# clock.net
KiCad netlist of a schematic drawn in Altium Designer
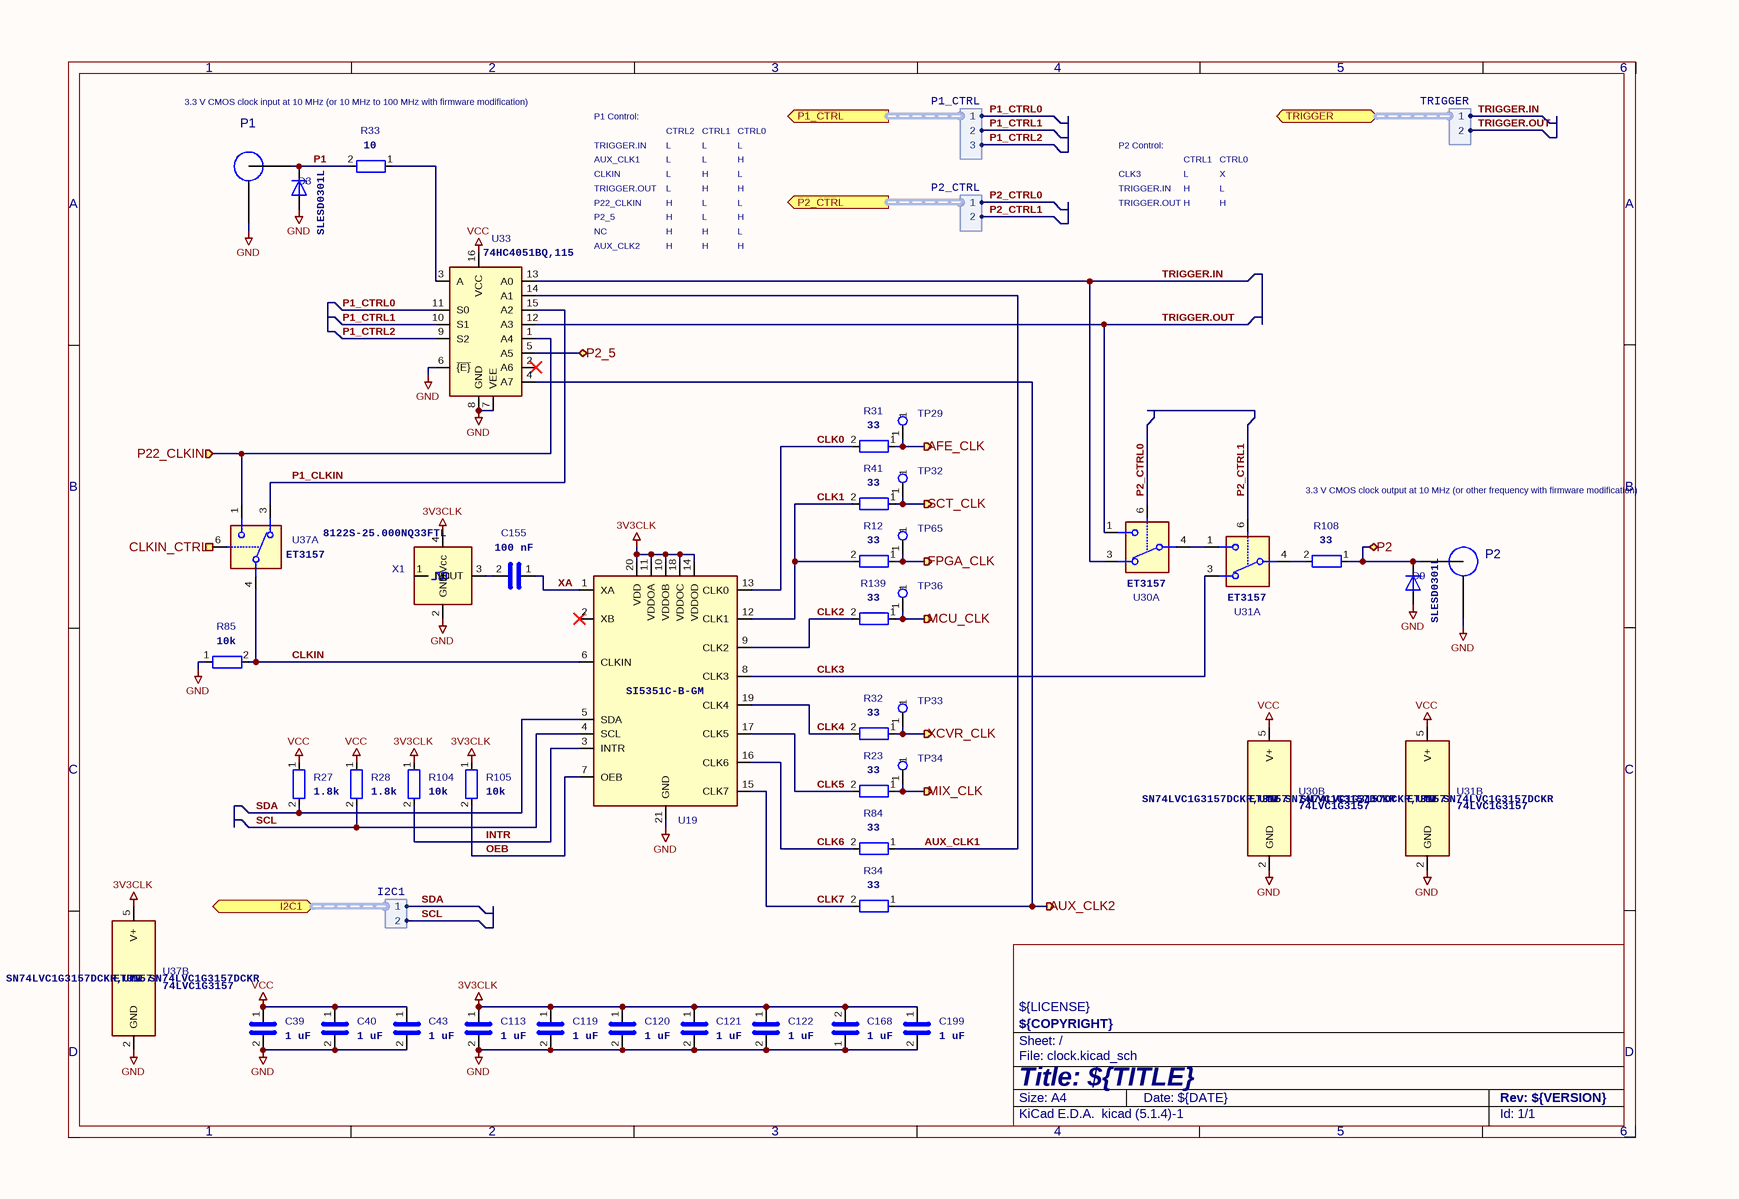
[diagram p0: clock.SchDoc]

(export (version "E")
  (design (tool "Eeschema 10.0.6"))
  (components
    (comp (ref "C39")
      (value "1 uF")
      (footprint "C_0402_1005Metric")
      (fields (field (name "MANUFACTURER") "Samsung") (field (name "PART NUMBER") "CL05A105KA5NQNC"))
      (libsource (lib "Device") (part "C"))
    )
    (comp (ref "C40")
      (value "1 uF")
      (footprint "C_0402_1005Metric")
      (fields (field (name "MANUFACTURER") "Samsung") (field (name "PART NUMBER") "CL05A105KA5NQNC"))
      (libsource (lib "Device") (part "C"))
    )
    (comp (ref "C43")
      (value "1 uF")
      (footprint "C_0402_1005Metric")
      (fields (field (name "MANUFACTURER") "Samsung") (field (name "PART NUMBER") "CL05A105KA5NQNC"))
      (libsource (lib "Device") (part "C"))
    )
    (comp (ref "C113")
      (value "1 uF")
      (footprint "C_0402_1005Metric")
      (fields (field (name "MANUFACTURER") "Samsung") (field (name "PART NUMBER") "CL05A105KA5NQNC"))
      (libsource (lib "Device") (part "C"))
    )
    (comp (ref "C119")
      (value "1 uF")
      (footprint "C_0402_1005Metric")
      (fields (field (name "MANUFACTURER") "Samsung") (field (name "PART NUMBER") "CL05A105KA5NQNC"))
      (libsource (lib "Device") (part "C"))
    )
    (comp (ref "C120")
      (value "1 uF")
      (footprint "C_0402_1005Metric")
      (fields (field (name "MANUFACTURER") "Samsung") (field (name "PART NUMBER") "CL05A105KA5NQNC"))
      (libsource (lib "Device") (part "C"))
    )
    (comp (ref "C121")
      (value "1 uF")
      (footprint "C_0402_1005Metric")
      (fields (field (name "MANUFACTURER") "Samsung") (field (name "PART NUMBER") "CL05A105KA5NQNC"))
      (libsource (lib "Device") (part "C"))
    )
    (comp (ref "C122")
      (value "1 uF")
      (footprint "C_0402_1005Metric")
      (fields (field (name "MANUFACTURER") "Samsung") (field (name "PART NUMBER") "CL05A105KA5NQNC"))
      (libsource (lib "Device") (part "C"))
    )
    (comp (ref "C155")
      (value "100 nF")
      (footprint "C_0402_1005Metric")
      (fields (field (name "MANUFACTURER") "Samsung") (field (name "PART NUMBER") "CL05A104KA5NNNC"))
      (libsource (lib "Device") (part "C"))
    )
    (comp (ref "C168")
      (value "1 uF")
      (footprint "C_0402_1005Metric")
      (fields (field (name "MANUFACTURER") "Samsung") (field (name "PART NUMBER") "CL05A105KA5NQNC"))
      (libsource (lib "Device") (part "C"))
    )
    (comp (ref "C199")
      (value "1 uF")
      (footprint "C_0402_1005Metric")
      (fields (field (name "MANUFACTURER") "Samsung") (field (name "PART NUMBER") "CL05A105KA5NQNC"))
      (libsource (lib "Device") (part "C"))
    )
    (comp (ref "D3")
      (value "TVS")
      (footprint "TSLP-2-19")
      (fields (field (name "MANUFACTURER") "Slkor") (field (name "PART NUMBER") "SLESD0301L"))
      (libsource (lib "Device") (part "D_Zener"))
    )
    (comp (ref "D9")
      (value "TVS")
      (footprint "TSLP-2-19")
      (fields (field (name "MANUFACTURER") "Slkor") (field (name "PART NUMBER") "SLESD0301L"))
      (libsource (lib "Device") (part "D_Zener"))
    )
    (comp (ref "P1")
      (value "SMA")
      (footprint "SMA_MyAntenna_A-SMA-KE-16.5A_EdgeMount")
      (fields (field (name "MANUFACTURER") "MyAntenna") (field (name "PART NUMBER") "A-SMA-KE-16.5A"))
      (libsource (lib "hackrf") (part "GSG-RF-CONN"))
    )
    (comp (ref "P2")
      (value "SMA")
      (footprint "SMA_MyAntenna_A-SMA-KE-16.5A_EdgeMount")
      (fields (field (name "MANUFACTURER") "MyAntenna") (field (name "PART NUMBER") "A-SMA-KE-16.5A"))
      (libsource (lib "hackrf") (part "GSG-RF-CONN"))
    )
    (comp (ref "R12")
      (value "33")
      (footprint "R_0201_0603Metric")
      (fields (field (name "MANUFACTURER") "Yageo") (field (name "PART NUMBER") "RC0201JR-0733RL"))
      (libsource (lib "") (part "R_1"))
    )
    (comp (ref "R23")
      (value "33")
      (footprint "R_0201_0603Metric")
      (fields (field (name "MANUFACTURER") "Yageo") (field (name "PART NUMBER") "RC0201JR-0733RL"))
      (libsource (lib "") (part "R_1"))
    )
    (comp (ref "R27")
      (value "1.8k")
      (footprint "R_0402_1005Metric")
      (fields (field (name "MANUFACTURER") "Yageo") (field (name "PART NUMBER") "RC0402JR-071K8L"))
      (libsource (lib "Device") (part "R"))
    )
    (comp (ref "R28")
      (value "1.8k")
      (footprint "R_0402_1005Metric")
      (fields (field (name "MANUFACTURER") "Yageo") (field (name "PART NUMBER") "RC0402JR-071K8L"))
      (libsource (lib "Device") (part "R"))
    )
    (comp (ref "R31")
      (value "33")
      (footprint "R_0201_0603Metric")
      (fields (field (name "MANUFACTURER") "Yageo") (field (name "PART NUMBER") "RC0201JR-0733RL"))
      (libsource (lib "") (part "R_1"))
    )
    (comp (ref "R32")
      (value "33")
      (footprint "R_0201_0603Metric")
      (fields (field (name "MANUFACTURER") "Yageo") (field (name "PART NUMBER") "RC0201JR-0733RL"))
      (libsource (lib "") (part "R_1"))
    )
    (comp (ref "R33")
      (value "10")
      (footprint "R_0201_0603Metric")
      (fields (field (name "MANUFACTURER") "Yageo") (field (name "PART NUMBER") "RC0201JR-0710RL"))
      (libsource (lib "") (part "R_1"))
    )
    (comp (ref "R34")
      (value "33")
      (footprint "R_0201_0603Metric")
      (fields (field (name "MANUFACTURER") "Yageo") (field (name "PART NUMBER") "RC0201JR-0733RL"))
      (libsource (lib "") (part "R_1"))
    )
    (comp (ref "R41")
      (value "33")
      (footprint "R_0201_0603Metric")
      (fields (field (name "MANUFACTURER") "Yageo") (field (name "PART NUMBER") "RC0201JR-0733RL"))
      (libsource (lib "") (part "R_1"))
    )
    (comp (ref "R84")
      (value "33")
      (footprint "R_0201_0603Metric")
      (fields (field (name "MANUFACTURER") "Yageo") (field (name "PART NUMBER") "RC0201JR-0733RL"))
      (libsource (lib "") (part "R_1"))
    )
    (comp (ref "R85")
      (value "10k")
      (footprint "R_0402_1005Metric")
      (fields (field (name "MANUFACTURER") "Yageo") (field (name "PART NUMBER") "RC0402JR-0710KL"))
      (libsource (lib "") (part "R_2"))
    )
    (comp (ref "R104")
      (value "10k")
      (footprint "R_0402_1005Metric")
      (fields (field (name "MANUFACTURER") "Yageo") (field (name "PART NUMBER") "RC0402JR-0710KL"))
      (libsource (lib "Device") (part "R"))
    )
    (comp (ref "R105")
      (value "10k")
      (footprint "R_0402_1005Metric")
      (fields (field (name "MANUFACTURER") "Yageo") (field (name "PART NUMBER") "RC0402JR-0710KL"))
      (libsource (lib "Device") (part "R"))
    )
    (comp (ref "R108")
      (value "33")
      (footprint "R_0201_0603Metric")
      (fields (field (name "MANUFACTURER") "Yageo") (field (name "PART NUMBER") "RC0201JR-0733RL"))
      (libsource (lib "") (part "R_1"))
    )
    (comp (ref "R139")
      (value "33")
      (footprint "R_0201_0603Metric")
      (fields (field (name "MANUFACTURER") "Yageo") (field (name "PART NUMBER") "RC0201JR-0733RL"))
      (libsource (lib "") (part "R_1"))
    )
    (comp (ref "TP29")
      (value "TestPoint")
      (footprint "TestPoint_Pad_D1.0mm")
      (libsource (lib "Connector") (part "TestPoint"))
    )
    (comp (ref "TP32")
      (value "TestPoint")
      (footprint "TestPoint_Pad_D1.0mm")
      (libsource (lib "Connector") (part "TestPoint"))
    )
    (comp (ref "TP33")
      (value "TestPoint")
      (footprint "TestPoint_Pad_D1.0mm")
      (libsource (lib "Connector") (part "TestPoint"))
    )
    (comp (ref "TP34")
      (value "TestPoint")
      (footprint "TestPoint_Pad_D1.0mm")
      (libsource (lib "Connector") (part "TestPoint"))
    )
    (comp (ref "TP36")
      (value "TestPoint")
      (footprint "TestPoint_Pad_D1.0mm")
      (libsource (lib "Connector") (part "TestPoint"))
    )
    (comp (ref "TP65")
      (value "TestPoint")
      (footprint "TestPoint_Pad_D1.0mm")
      (libsource (lib "Connector") (part "TestPoint"))
    )
    (comp (ref "U19")
      (value "SI5351C")
      (footprint "QFN-20-1EP_4x4mm_P0.5mm_EP2.7x2.7mm_ThermalVias")
      (fields
        (field (name "MANUFACTURER") "Silicon Laboratories Inc")
        (field (name "PART NUMBER") "SI5351C-B-GM")
      )
      (libsource (lib "Oscillator") (part "Si5351C-B-GM"))
    )
    (comp (ref "U30")
      (value "74LVC1G3157")
      (footprint "SOT-363_SC-70-6")
      (fields
        (field (name "MANUFACTURER") "UMW")
        (field (name "PART NUMBER") "ET3157")
        (field (name "SUBSTITUTION") "SN74LVC1G3157DCKR, TI SN74LVC1G3157DCKR")
      )
      (libsource (lib "Analog_Switch") (part "NC7SB3157P6X"))
    )
    (comp (ref "U31")
      (value "74LVC1G3157")
      (footprint "SOT-363_SC-70-6")
      (fields
        (field (name "MANUFACTURER") "UMW")
        (field (name "PART NUMBER") "ET3157")
        (field (name "SUBSTITUTION") "SN74LVC1G3157DCKR, TI SN74LVC1G3157DCKR")
      )
      (libsource (lib "") (part "NC7SB3157P6X_1"))
    )
    (comp (ref "U33")
      (value "74HC4051")
      (footprint "DHVQFN-16-1EP_2.5x3.5mm_P0.5mm_EP1x2mm")
      (fields (field (name "MANUFACTURER") "Nexperia") (field (name "PART NUMBER") "74HC4051BQ,115"))
      (libsource (lib "74xx") (part "74HC4051"))
    )
    (comp (ref "U37")
      (value "74LVC1G3157")
      (footprint "SOT-363_SC-70-6")
      (fields
        (field (name "MANUFACTURER") "UMW")
        (field (name "PART NUMBER") "ET3157")
        (field (name "SUBSTITUTION") "SN74LVC1G3157DCKR, TI SN74LVC1G3157DCKR")
      )
      (libsource (lib "Analog_Switch") (part "NC7SB3157P6X"))
    )
    (comp (ref "X1")
      (value "TCXO")
      (footprint "Oscillator_SMD_SeikoEpson_TG2520SMN-xxx-xxxxxx-4Pin_2.5x2.0mm")
      (fields (field (name "MANUFACTURER") "HCI") (field (name "PART NUMBER") "8122S-25.000NQ33FTL"))
      (libsource (lib "Oscillator") (part "TG2520SMN-xx.xxxxxxMhz-xxxxNM"))
    )
  )
  (nets
    (net (code "5") (name "/AFE_CLK") (class "Default")
      (node (ref "R31") (pin "1") (pinfunction "1_1") (pintype "passive"))
      (node (ref "TP29") (pin "1") (pinfunction "1_1") (pintype "passive"))
    )
    (net (code "6") (name "/AUX_CLK1") (class "Default")
      (node (ref "R84") (pin "1") (pinfunction "1_1") (pintype "passive"))
      (node (ref "U33") (pin "14") (pinfunction "A1_14") (pintype "passive"))
    )
    (net (code "7") (name "/AUX_CLK2") (class "Default")
      (node (ref "R34") (pin "1") (pinfunction "1_1") (pintype "passive"))
      (node (ref "U33") (pin "4") (pinfunction "A7_4") (pintype "passive"))
    )
    (net (code "8") (name "/CLK0") (class "Default")
      (node (ref "R31") (pin "2") (pinfunction "2_2") (pintype "passive"))
      (node (ref "U19") (pin "13") (pinfunction "CLK0_13") (pintype "passive"))
    )
    (net (code "9") (name "/CLK1") (class "Default")
      (node (ref "R12") (pin "2") (pinfunction "2_2") (pintype "passive"))
      (node (ref "R41") (pin "2") (pinfunction "2_2") (pintype "passive"))
      (node (ref "U19") (pin "12") (pinfunction "CLK1_12") (pintype "passive"))
    )
    (net (code "10") (name "/CLK2") (class "Default")
      (node (ref "R139") (pin "2") (pinfunction "2_2") (pintype "passive"))
      (node (ref "U19") (pin "9") (pinfunction "CLK2_9") (pintype "passive"))
    )
    (net (code "11") (name "/CLK3") (class "Default")
      (node (ref "U19") (pin "8") (pinfunction "CLK3_8") (pintype "passive"))
      (node (ref "U31") (pin "3") (pinfunction "3_3") (pintype "passive"))
    )
    (net (code "12") (name "/CLK4") (class "Default")
      (node (ref "R32") (pin "2") (pinfunction "2_2") (pintype "passive"))
      (node (ref "U19") (pin "19") (pinfunction "CLK4_19") (pintype "passive"))
    )
    (net (code "13") (name "/CLK5") (class "Default")
      (node (ref "R23") (pin "2") (pinfunction "2_2") (pintype "passive"))
      (node (ref "U19") (pin "17") (pinfunction "CLK5_17") (pintype "passive"))
    )
    (net (code "14") (name "/CLK6") (class "Default")
      (node (ref "R84") (pin "2") (pinfunction "2_2") (pintype "passive"))
      (node (ref "U19") (pin "16") (pinfunction "CLK6_16") (pintype "passive"))
    )
    (net (code "15") (name "/CLK7") (class "Default")
      (node (ref "R34") (pin "2") (pinfunction "2_2") (pintype "passive"))
      (node (ref "U19") (pin "15") (pinfunction "CLK7_15") (pintype "passive"))
    )
    (net (code "16") (name "/CLKIN") (class "Default")
      (node (ref "R85") (pin "2") (pinfunction "2_2") (pintype "passive"))
      (node (ref "U19") (pin "6") (pinfunction "CLKIN_6") (pintype "passive"))
      (node (ref "U37") (pin "4") (pinfunction "4_4") (pintype "passive"))
    )
    (net (code "17") (name "/CLKIN_CTRL") (class "Default")
      (node (ref "U37") (pin "6") (pinfunction "6_6") (pintype "passive"))
    )
    (net (code "18") (name "/FPGA_CLK") (class "Default")
      (node (ref "R12") (pin "1") (pinfunction "1_1") (pintype "passive"))
      (node (ref "TP65") (pin "1") (pinfunction "1_1") (pintype "passive"))
    )
    (net (code "19") (name "/INTR") (class "Default")
      (node (ref "R104") (pin "2") (pinfunction "2_2") (pintype "passive"))
      (node (ref "U19") (pin "3") (pinfunction "INTR_3") (pintype "passive"))
    )
    (net (code "20") (name "/MCU_CLK") (class "Default")
      (node (ref "R139") (pin "1") (pinfunction "1_1") (pintype "passive"))
      (node (ref "TP36") (pin "1") (pinfunction "1_1") (pintype "passive"))
    )
    (net (code "21") (name "/MIX_CLK") (class "Default")
      (node (ref "R23") (pin "1") (pinfunction "1_1") (pintype "passive"))
      (node (ref "TP34") (pin "1") (pinfunction "1_1") (pintype "passive"))
    )
    (net (code "22") (name "/OEB") (class "Default")
      (node (ref "R105") (pin "2") (pinfunction "2_2") (pintype "passive"))
      (node (ref "U19") (pin "7") (pinfunction "OEB_7") (pintype "passive"))
    )
    (net (code "23") (name "/P1") (class "Default")
      (node (ref "D3") (pin "1") (pinfunction "K_1") (pintype "passive"))
      (node (ref "P1") (pin "1") (pinfunction "RF_1") (pintype "passive"))
      (node (ref "R33") (pin "2") (pinfunction "2_2") (pintype "passive"))
    )
    (net (code "24") (name "/P1_CLKIN") (class "Default")
      (node (ref "U33") (pin "15") (pinfunction "A2_15") (pintype "passive"))
      (node (ref "U37") (pin "3") (pinfunction "3_3") (pintype "passive"))
    )
    (net (code "25") (name "/P1_CTRL0") (class "Default")
      (node (ref "U33") (pin "11") (pinfunction "S0_11") (pintype "passive"))
    )
    (net (code "26") (name "/P1_CTRL1") (class "Default")
      (node (ref "U33") (pin "10") (pinfunction "S1_10") (pintype "passive"))
    )
    (net (code "27") (name "/P1_CTRL2") (class "Default")
      (node (ref "U33") (pin "9") (pinfunction "S2_9") (pintype "passive"))
    )
    (net (code "28") (name "/P2") (class "Default")
      (node (ref "D9") (pin "1") (pinfunction "K_1") (pintype "passive"))
      (node (ref "P2") (pin "1") (pinfunction "RF_1") (pintype "passive"))
      (node (ref "R108") (pin "1") (pinfunction "1_1") (pintype "passive"))
    )
    (net (code "29") (name "/P2_5") (class "Default")
      (node (ref "U33") (pin "5") (pinfunction "A5_5") (pintype "passive"))
    )
    (net (code "30") (name "/P2_CTRL0") (class "Default")
      (node (ref "U30") (pin "6") (pinfunction "6_6") (pintype "passive"))
    )
    (net (code "31") (name "/P2_CTRL1") (class "Default")
      (node (ref "U31") (pin "6") (pinfunction "6_6") (pintype "passive"))
    )
    (net (code "32") (name "/P22_CLKIN") (class "Default")
      (node (ref "U33") (pin "1") (pinfunction "A4_1") (pintype "passive"))
      (node (ref "U37") (pin "1") (pinfunction "1_1") (pintype "passive"))
    )
    (net (code "33") (name "/SCL") (class "Default")
      (node (ref "R28") (pin "2") (pinfunction "2_2") (pintype "passive"))
      (node (ref "U19") (pin "4") (pinfunction "SCL_4") (pintype "passive"))
    )
    (net (code "34") (name "/SCT_CLK") (class "Default")
      (node (ref "R41") (pin "1") (pinfunction "1_1") (pintype "passive"))
      (node (ref "TP32") (pin "1") (pinfunction "1_1") (pintype "passive"))
    )
    (net (code "35") (name "/SDA") (class "Default")
      (node (ref "R27") (pin "2") (pinfunction "2_2") (pintype "passive"))
      (node (ref "U19") (pin "5") (pinfunction "SDA_5") (pintype "passive"))
    )
    (net (code "36") (name "/TRIGGER.IN") (class "Default")
      (node (ref "U30") (pin "3") (pinfunction "3_3") (pintype "passive"))
      (node (ref "U33") (pin "13") (pinfunction "A0_13") (pintype "passive"))
    )
    (net (code "37") (name "/TRIGGER.OUT") (class "Default")
      (node (ref "U30") (pin "1") (pinfunction "1_1") (pintype "passive"))
      (node (ref "U33") (pin "12") (pinfunction "A3_12") (pintype "passive"))
    )
    (net (code "38") (name "/XA") (class "Default")
      (node (ref "C155") (pin "1") (pinfunction "1_1") (pintype "passive"))
      (node (ref "U19") (pin "1") (pinfunction "XA_1") (pintype "passive"))
    )
    (net (code "39") (name "/XCVR_CLK") (class "Default")
      (node (ref "R32") (pin "1") (pinfunction "1_1") (pintype "passive"))
      (node (ref "TP33") (pin "1") (pinfunction "1_1") (pintype "passive"))
    )
    (net (code "44") (name "3V3CLK") (class "Default")
      (node (ref "C113") (pin "1") (pinfunction "1_1") (pintype "passive"))
      (node (ref "C119") (pin "1") (pinfunction "1_1") (pintype "passive"))
      (node (ref "C120") (pin "1") (pinfunction "1_1") (pintype "passive"))
      (node (ref "C121") (pin "1") (pinfunction "1_1") (pintype "passive"))
      (node (ref "C122") (pin "1") (pinfunction "1_1") (pintype "passive"))
      (node (ref "C168") (pin "2") (pinfunction "2_2") (pintype "passive"))
      (node (ref "C199") (pin "1") (pinfunction "1_1") (pintype "passive"))
      (node (ref "R104") (pin "1") (pinfunction "1_1") (pintype "passive"))
      (node (ref "R105") (pin "1") (pinfunction "1_1") (pintype "passive"))
      (node (ref "U19") (pin "10") (pinfunction "VDDOB_10") (pintype "passive"))
      (node (ref "U19") (pin "11") (pinfunction "VDDOA_11") (pintype "passive"))
      (node (ref "U19") (pin "14") (pinfunction "VDDOD_14") (pintype "passive"))
      (node (ref "U19") (pin "18") (pinfunction "VDDOC_18") (pintype "passive"))
      (node (ref "U19") (pin "20") (pinfunction "VDD_20") (pintype "passive"))
      (node (ref "U37") (pin "5") (pinfunction "V+_5") (pintype "passive"))
      (node (ref "X1") (pin "4") (pinfunction "Vcc_4") (pintype "passive"))
    )
    (net (code "45") (name "GND") (class "Default")
      (node (ref "C113") (pin "2") (pinfunction "2_2") (pintype "passive"))
      (node (ref "C119") (pin "2") (pinfunction "2_2") (pintype "passive"))
      (node (ref "C120") (pin "2") (pinfunction "2_2") (pintype "passive"))
      (node (ref "C121") (pin "2") (pinfunction "2_2") (pintype "passive"))
      (node (ref "C122") (pin "2") (pinfunction "2_2") (pintype "passive"))
      (node (ref "C168") (pin "1") (pinfunction "1_1") (pintype "passive"))
      (node (ref "C199") (pin "2") (pinfunction "2_2") (pintype "passive"))
      (node (ref "C39") (pin "2") (pinfunction "2_2") (pintype "passive"))
      (node (ref "C40") (pin "2") (pinfunction "2_2") (pintype "passive"))
      (node (ref "C43") (pin "2") (pinfunction "2_2") (pintype "passive"))
      (node (ref "D3") (pin "2") (pinfunction "A_2") (pintype "passive"))
      (node (ref "D9") (pin "2") (pinfunction "A_2") (pintype "passive"))
      (node (ref "P1") (pin "2") (pinfunction "GND_2") (pintype "passive"))
      (node (ref "P2") (pin "2") (pinfunction "GND_2") (pintype "passive"))
      (node (ref "R85") (pin "1") (pinfunction "1_1") (pintype "passive"))
      (node (ref "U19") (pin "21") (pinfunction "GND_21") (pintype "passive"))
      (node (ref "U30") (pin "2") (pinfunction "GND_2") (pintype "passive"))
      (node (ref "U31") (pin "2") (pinfunction "GND_2") (pintype "passive"))
      (node (ref "U33") (pin "6") (pinfunction "~{{E}}_6") (pintype "passive"))
      (node (ref "U33") (pin "7") (pinfunction "VEE_7") (pintype "passive"))
      (node (ref "U33") (pin "8") (pinfunction "GND_8") (pintype "passive"))
      (node (ref "U37") (pin "2") (pinfunction "GND_2") (pintype "passive"))
      (node (ref "X1") (pin "2") (pinfunction "GND_2") (pintype "passive"))
    )
    (net (code "46") (name "Net-(R108-Pad2)") (class "Default")
      (node (ref "R108") (pin "2") (pinfunction "2_2") (pintype "passive"))
      (node (ref "U31") (pin "4") (pinfunction "4_4") (pintype "passive"))
    )
    (net (code "47") (name "Net-(U30-Pad4)") (class "Default")
      (node (ref "U30") (pin "4") (pinfunction "4_4") (pintype "passive"))
      (node (ref "U31") (pin "1") (pinfunction "1_1") (pintype "passive"))
    )
    (net (code "48") (name "Net-(U33-A)") (class "Default")
      (node (ref "R33") (pin "1") (pinfunction "1_1") (pintype "passive"))
      (node (ref "U33") (pin "3") (pinfunction "A_3") (pintype "passive"))
    )
    (net (code "49") (name "Net-(X1-OUT)") (class "Default")
      (node (ref "C155") (pin "2") (pinfunction "2_2") (pintype "passive"))
      (node (ref "X1") (pin "3") (pinfunction "OUT_3") (pintype "passive"))
    )
    (net (code "50") (name "VCC") (class "Default")
      (node (ref "C39") (pin "1") (pinfunction "1_1") (pintype "passive"))
      (node (ref "C40") (pin "1") (pinfunction "1_1") (pintype "passive"))
      (node (ref "C43") (pin "1") (pinfunction "1_1") (pintype "passive"))
      (node (ref "R27") (pin "1") (pinfunction "1_1") (pintype "passive"))
      (node (ref "R28") (pin "1") (pinfunction "1_1") (pintype "passive"))
      (node (ref "U30") (pin "5") (pinfunction "V+_5") (pintype "passive"))
      (node (ref "U31") (pin "5") (pinfunction "V+_5") (pintype "passive"))
      (node (ref "U33") (pin "16") (pinfunction "VCC_16") (pintype "passive"))
    )
    (net (code "51") (name "unconnected-(U19-XB-Pad2)") (class "Default")
      (node (ref "U19") (pin "2") (pinfunction "XB_2") (pintype "passive+no_connect"))
    )
    (net (code "52") (name "unconnected-(U33-A6-Pad2)") (class "Default")
      (node (ref "U33") (pin "2") (pinfunction "A6_2") (pintype "passive+no_connect"))
    )
    (net (code "53") (name "unconnected-(X1-NC-Pad1)") (class "Default")
      (node (ref "X1") (pin "1") (pinfunction "NC_1") (pintype "passive"))
    )
  )
)
